# esp07_12_shift_inout.net
KiCad netlist of a schematic drawn in EAGLE
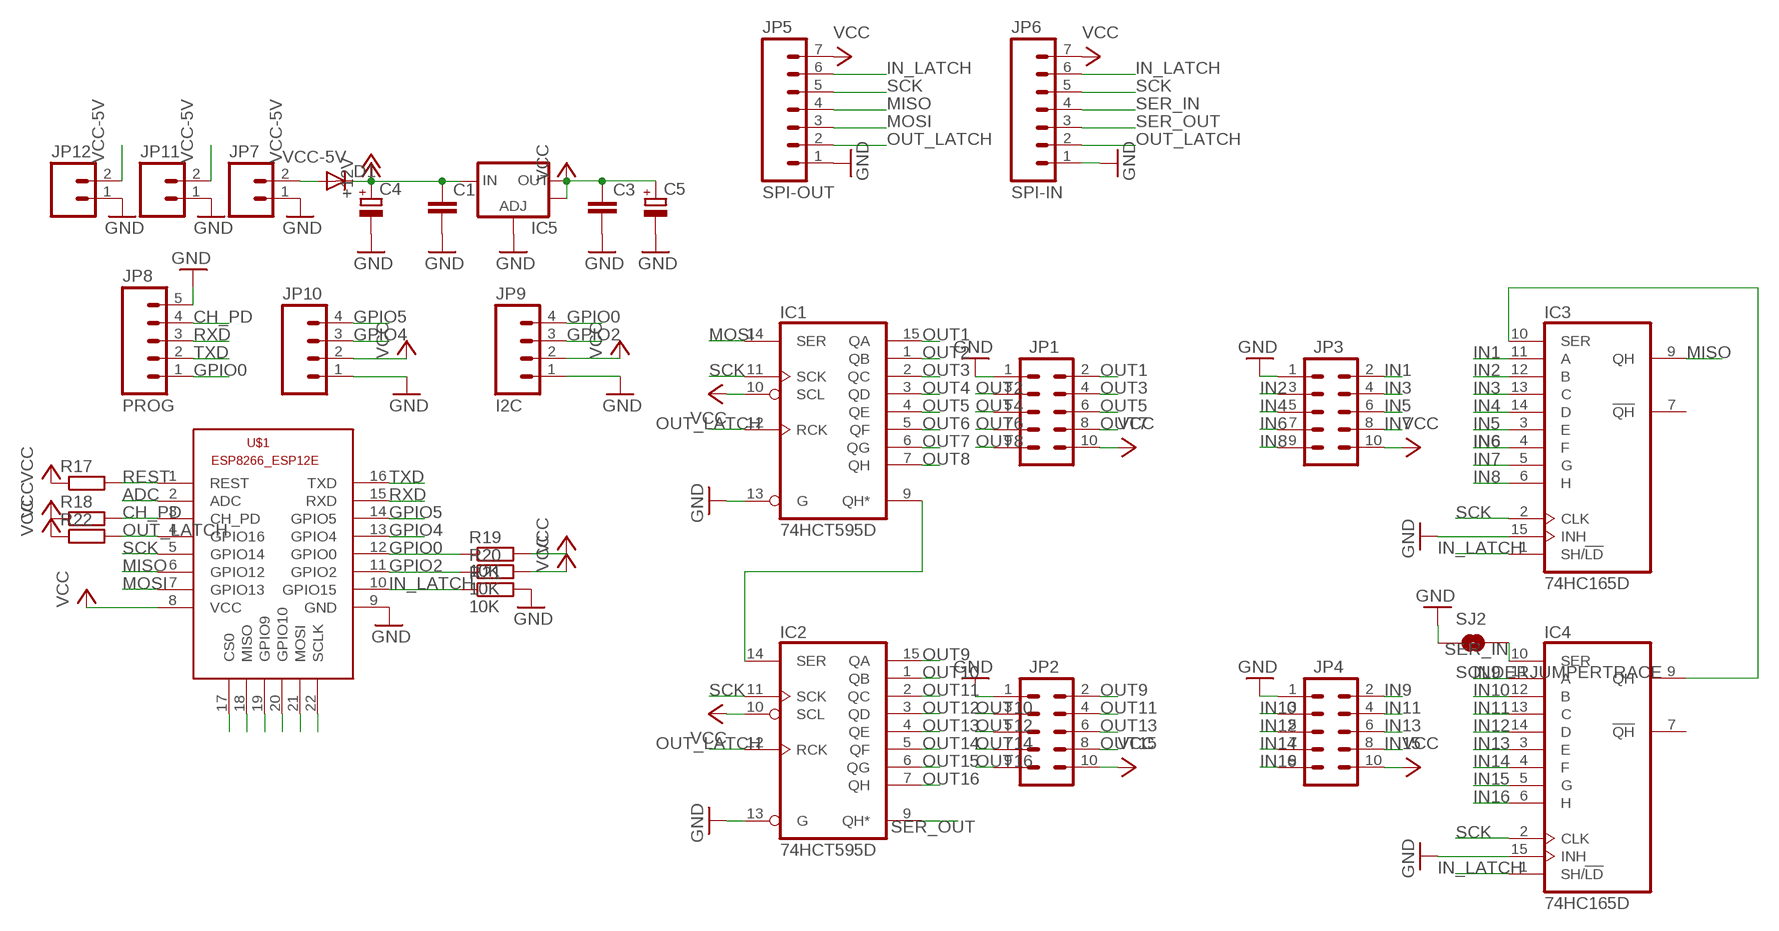
[diagram p0: schematic, sheet 1]

(export (version "E")
  (design (tool "Eeschema 10.0.6"))
  (components
    (comp (ref "C1")
      (value "C-EUC0805")
      (footprint "eagle-import:C0805")
      (libsource (lib "eagle-import") (part "C-EUC0805"))
    )
    (comp (ref "C3")
      (value "C-EUC0805")
      (footprint "eagle-import:C0805")
      (libsource (lib "eagle-import") (part "C-EUC0805"))
    )
    (comp (ref "C4")
      (value "CPOL-EUD/7343-31R")
      (footprint "eagle-import:D_7343-31R")
      (libsource (lib "eagle-import") (part "CPOL-EUD/7343-31R"))
    )
    (comp (ref "C5")
      (value "CPOL-EUD/7343-31R")
      (footprint "eagle-import:D_7343-31R")
      (libsource (lib "eagle-import") (part "CPOL-EUD/7343-31R"))
    )
    (comp (ref "D1")
      (value "DIODE-DO214AC")
      (footprint "eagle-import:DO214AC")
      (libsource (lib "eagle-import") (part "DIODE-DO214AC"))
    )
    (comp (ref "IC1")
      (value "74HCT595D")
      (footprint "eagle-import:SO16")
      (libsource (lib "eagle-import") (part "74595DHCT"))
    )
    (comp (ref "IC2")
      (value "74HCT595D")
      (footprint "eagle-import:SO16")
      (libsource (lib "eagle-import") (part "74595DHCT"))
    )
    (comp (ref "IC3")
      (value "74HC165D")
      (footprint "eagle-import:SO16")
      (libsource (lib "eagle-import") (part "74165DHC"))
    )
    (comp (ref "IC4")
      (value "74HC165D")
      (footprint "eagle-import:SO16")
      (libsource (lib "eagle-import") (part "74165DHC"))
    )
    (comp (ref "IC5")
      (value "V_REG_LM1117SOT223")
      (footprint "eagle-import:SOT223")
      (libsource (lib "eagle-import") (part "V_REG_LM1117SOT223"))
    )
    (comp (ref "JP1")
      (value "M05X2SHD")
      (footprint "eagle-import:2X5-SHROUDED")
      (libsource (lib "eagle-import") (part "M05X2SHD"))
    )
    (comp (ref "JP2")
      (value "M05X2SHD")
      (footprint "eagle-import:2X5-SHROUDED")
      (libsource (lib "eagle-import") (part "M05X2SHD"))
    )
    (comp (ref "JP3")
      (value "M05X2SHD")
      (footprint "eagle-import:2X5-SHROUDED")
      (libsource (lib "eagle-import") (part "M05X2SHD"))
    )
    (comp (ref "JP4")
      (value "M05X2SHD")
      (footprint "eagle-import:2X5-SHROUDED")
      (libsource (lib "eagle-import") (part "M05X2SHD"))
    )
    (comp (ref "JP5")
      (value "SPI-OUT")
      (footprint "eagle-import:1X07")
      (libsource (lib "eagle-import") (part "M07"))
    )
    (comp (ref "JP6")
      (value "SPI-IN")
      (footprint "eagle-import:1X07")
      (libsource (lib "eagle-import") (part "M07"))
    )
    (comp (ref "JP7")
      (value "M02PTH3")
      (footprint "eagle-import:1X02_LONGPADS")
      (libsource (lib "eagle-import") (part "M02PTH3"))
    )
    (comp (ref "JP8")
      (value "PROG")
      (footprint "eagle-import:1X05")
      (libsource (lib "eagle-import") (part "M05PTH"))
    )
    (comp (ref "JP9")
      (value "I2C")
      (footprint "eagle-import:1X04")
      (libsource (lib "eagle-import") (part "M04PTH"))
    )
    (comp (ref "JP10")
      (value "M04PTH")
      (footprint "eagle-import:1X04")
      (libsource (lib "eagle-import") (part "M04PTH"))
    )
    (comp (ref "JP11")
      (value "M02PTH")
      (footprint "eagle-import:1X02")
      (libsource (lib "eagle-import") (part "M02PTH"))
    )
    (comp (ref "JP12")
      (value "M02PTH")
      (footprint "eagle-import:1X02")
      (libsource (lib "eagle-import") (part "M02PTH"))
    )
    (comp (ref "R17")
      (value "R-EU_R0603")
      (footprint "eagle-import:R0603")
      (libsource (lib "eagle-import") (part "R-EU_R0603"))
    )
    (comp (ref "R18")
      (value "R-EU_R0603")
      (footprint "eagle-import:R0603")
      (libsource (lib "eagle-import") (part "R-EU_R0603"))
    )
    (comp (ref "R19")
      (value "10K")
      (footprint "eagle-import:R0603")
      (libsource (lib "eagle-import") (part "R-EU_R0603"))
    )
    (comp (ref "R20")
      (value "10K")
      (footprint "eagle-import:R0603")
      (libsource (lib "eagle-import") (part "R-EU_R0603"))
    )
    (comp (ref "R21")
      (value "10K")
      (footprint "eagle-import:R0603")
      (libsource (lib "eagle-import") (part "R-EU_R0603"))
    )
    (comp (ref "R22")
      (value "R-EU_R0603")
      (footprint "eagle-import:R0603")
      (libsource (lib "eagle-import") (part "R-EU_R0603"))
    )
    (comp (ref "SJ2")
      (value "SOLDERJUMPERTRACE")
      (footprint "eagle-import:SJ_2S-TRACE")
      (libsource (lib "eagle-import") (part "SOLDERJUMPERTRACE"))
    )
    (comp (ref "U$1")
      (value "ESP8266-12EESP8266-ESP12E")
      (footprint "eagle-import:ESP8266-ESP12E")
      (libsource (lib "eagle-import") (part "ESP8266-12EESP8266-ESP12E"))
    )
  )
  (nets
    (net (code "1") (name "+12V") (class "Default")
      (node (ref "C1") (pin "1") (pinfunction "1_1") (pintype "passive"))
      (node (ref "C4") (pin "+") (pinfunction "+_+") (pintype "passive"))
      (node (ref "D1") (pin "C") (pinfunction "C_C") (pintype "passive"))
      (node (ref "IC5") (pin "3") (pinfunction "IN_3") (pintype "input"))
    )
    (net (code "2") (name "/ADC") (class "Default")
      (node (ref "U$1") (pin "2") (pinfunction "ADC_2") (pintype "bidirectional"))
    )
    (net (code "3") (name "/CH_PD") (class "Default")
      (node (ref "JP8") (pin "4") (pinfunction "4_4") (pintype "passive"))
      (node (ref "R18") (pin "2") (pinfunction "2_2") (pintype "passive"))
      (node (ref "U$1") (pin "3") (pinfunction "CH_PD_3") (pintype "bidirectional"))
    )
    (net (code "4") (name "/GPIO0") (class "Default")
      (node (ref "JP8") (pin "1") (pinfunction "1_1") (pintype "passive"))
      (node (ref "JP9") (pin "4") (pinfunction "4_4") (pintype "passive"))
      (node (ref "R19") (pin "1") (pinfunction "1_1") (pintype "passive"))
      (node (ref "U$1") (pin "12") (pinfunction "GPIO0_12") (pintype "bidirectional"))
    )
    (net (code "5") (name "/GPIO2") (class "Default")
      (node (ref "JP9") (pin "3") (pinfunction "3_3") (pintype "passive"))
      (node (ref "R20") (pin "1") (pinfunction "1_1") (pintype "passive"))
      (node (ref "U$1") (pin "11") (pinfunction "GPIO2_11") (pintype "bidirectional"))
    )
    (net (code "6") (name "/GPIO4") (class "Default")
      (node (ref "JP10") (pin "3") (pinfunction "3_3") (pintype "passive"))
      (node (ref "U$1") (pin "13") (pinfunction "GPIO4_13") (pintype "bidirectional"))
    )
    (net (code "7") (name "/GPIO5") (class "Default")
      (node (ref "JP10") (pin "4") (pinfunction "4_4") (pintype "passive"))
      (node (ref "U$1") (pin "14") (pinfunction "GPIO5_14") (pintype "bidirectional"))
    )
    (net (code "8") (name "/IN1") (class "Default")
      (node (ref "IC3") (pin "11") (pinfunction "A_11") (pintype "input"))
      (node (ref "JP3") (pin "2") (pinfunction "2_2") (pintype "passive"))
    )
    (net (code "9") (name "/IN2") (class "Default")
      (node (ref "IC3") (pin "12") (pinfunction "B_12") (pintype "input"))
      (node (ref "JP3") (pin "3") (pinfunction "3_3") (pintype "passive"))
    )
    (net (code "10") (name "/IN3") (class "Default")
      (node (ref "IC3") (pin "13") (pinfunction "C_13") (pintype "input"))
      (node (ref "JP3") (pin "4") (pinfunction "4_4") (pintype "passive"))
    )
    (net (code "11") (name "/IN4") (class "Default")
      (node (ref "IC3") (pin "14") (pinfunction "D_14") (pintype "input"))
      (node (ref "JP3") (pin "5") (pinfunction "5_5") (pintype "passive"))
    )
    (net (code "12") (name "/IN5") (class "Default")
      (node (ref "IC3") (pin "3") (pinfunction "E_3") (pintype "input"))
      (node (ref "JP3") (pin "6") (pinfunction "6_6") (pintype "passive"))
    )
    (net (code "13") (name "/IN6") (class "Default")
      (node (ref "IC3") (pin "4") (pinfunction "F_4") (pintype "input"))
      (node (ref "JP3") (pin "7") (pinfunction "7_7") (pintype "passive"))
    )
    (net (code "14") (name "/IN7") (class "Default")
      (node (ref "IC3") (pin "5") (pinfunction "G_5") (pintype "input"))
      (node (ref "JP3") (pin "8") (pinfunction "8_8") (pintype "passive"))
    )
    (net (code "15") (name "/IN8") (class "Default")
      (node (ref "IC3") (pin "6") (pinfunction "H_6") (pintype "input"))
      (node (ref "JP3") (pin "9") (pinfunction "9_9") (pintype "passive"))
    )
    (net (code "16") (name "/IN9") (class "Default")
      (node (ref "IC4") (pin "11") (pinfunction "A_11") (pintype "input"))
      (node (ref "JP4") (pin "2") (pinfunction "2_2") (pintype "passive"))
    )
    (net (code "17") (name "/IN10") (class "Default")
      (node (ref "IC4") (pin "12") (pinfunction "B_12") (pintype "input"))
      (node (ref "JP4") (pin "3") (pinfunction "3_3") (pintype "passive"))
    )
    (net (code "18") (name "/IN11") (class "Default")
      (node (ref "IC4") (pin "13") (pinfunction "C_13") (pintype "input"))
      (node (ref "JP4") (pin "4") (pinfunction "4_4") (pintype "passive"))
    )
    (net (code "19") (name "/IN12") (class "Default")
      (node (ref "IC4") (pin "14") (pinfunction "D_14") (pintype "input"))
      (node (ref "JP4") (pin "5") (pinfunction "5_5") (pintype "passive"))
    )
    (net (code "20") (name "/IN13") (class "Default")
      (node (ref "IC4") (pin "3") (pinfunction "E_3") (pintype "input"))
      (node (ref "JP4") (pin "6") (pinfunction "6_6") (pintype "passive"))
    )
    (net (code "21") (name "/IN14") (class "Default")
      (node (ref "IC4") (pin "4") (pinfunction "F_4") (pintype "input"))
      (node (ref "JP4") (pin "7") (pinfunction "7_7") (pintype "passive"))
    )
    (net (code "22") (name "/IN15") (class "Default")
      (node (ref "IC4") (pin "5") (pinfunction "G_5") (pintype "input"))
      (node (ref "JP4") (pin "8") (pinfunction "8_8") (pintype "passive"))
    )
    (net (code "23") (name "/IN16") (class "Default")
      (node (ref "IC4") (pin "6") (pinfunction "H_6") (pintype "input"))
      (node (ref "JP4") (pin "9") (pinfunction "9_9") (pintype "passive"))
    )
    (net (code "24") (name "/IN_LATCH") (class "Default")
      (node (ref "IC3") (pin "1") (pinfunction "SH/~{LD}_1") (pintype "input"))
      (node (ref "IC4") (pin "1") (pinfunction "SH/~{LD}_1") (pintype "input"))
      (node (ref "JP5") (pin "6") (pinfunction "6_6") (pintype "passive"))
      (node (ref "JP6") (pin "6") (pinfunction "6_6") (pintype "passive"))
      (node (ref "R21") (pin "1") (pinfunction "1_1") (pintype "passive"))
      (node (ref "U$1") (pin "10") (pinfunction "GPIO15_10") (pintype "bidirectional"))
    )
    (net (code "25") (name "/MISO") (class "Default")
      (node (ref "IC3") (pin "9") (pinfunction "QH_9") (pintype "output"))
      (node (ref "JP5") (pin "4") (pinfunction "4_4") (pintype "passive"))
      (node (ref "U$1") (pin "6") (pinfunction "GPIO12_6") (pintype "bidirectional"))
    )
    (net (code "26") (name "/MOSI") (class "Default")
      (node (ref "IC1") (pin "14") (pinfunction "SER_14") (pintype "input"))
      (node (ref "JP5") (pin "3") (pinfunction "3_3") (pintype "passive"))
      (node (ref "U$1") (pin "7") (pinfunction "GPIO13_7") (pintype "bidirectional"))
    )
    (net (code "27") (name "/OUT1") (class "Default")
      (node (ref "IC1") (pin "15") (pinfunction "QA_15") (pintype "tri_state"))
      (node (ref "JP1") (pin "2") (pinfunction "2_2") (pintype "passive"))
    )
    (net (code "28") (name "/OUT2") (class "Default")
      (node (ref "IC1") (pin "1") (pinfunction "QB_1") (pintype "tri_state"))
      (node (ref "JP1") (pin "3") (pinfunction "3_3") (pintype "passive"))
    )
    (net (code "29") (name "/OUT3") (class "Default")
      (node (ref "IC1") (pin "2") (pinfunction "QC_2") (pintype "tri_state"))
      (node (ref "JP1") (pin "4") (pinfunction "4_4") (pintype "passive"))
    )
    (net (code "30") (name "/OUT4") (class "Default")
      (node (ref "IC1") (pin "3") (pinfunction "QD_3") (pintype "tri_state"))
      (node (ref "JP1") (pin "5") (pinfunction "5_5") (pintype "passive"))
    )
    (net (code "31") (name "/OUT5") (class "Default")
      (node (ref "IC1") (pin "4") (pinfunction "QE_4") (pintype "tri_state"))
      (node (ref "JP1") (pin "6") (pinfunction "6_6") (pintype "passive"))
    )
    (net (code "32") (name "/OUT6") (class "Default")
      (node (ref "IC1") (pin "5") (pinfunction "QF_5") (pintype "tri_state"))
      (node (ref "JP1") (pin "7") (pinfunction "7_7") (pintype "passive"))
    )
    (net (code "33") (name "/OUT7") (class "Default")
      (node (ref "IC1") (pin "6") (pinfunction "QG_6") (pintype "tri_state"))
      (node (ref "JP1") (pin "8") (pinfunction "8_8") (pintype "passive"))
    )
    (net (code "34") (name "/OUT8") (class "Default")
      (node (ref "IC1") (pin "7") (pinfunction "QH_7") (pintype "tri_state"))
      (node (ref "JP1") (pin "9") (pinfunction "9_9") (pintype "passive"))
    )
    (net (code "35") (name "/OUT9") (class "Default")
      (node (ref "IC2") (pin "15") (pinfunction "QA_15") (pintype "tri_state"))
      (node (ref "JP2") (pin "2") (pinfunction "2_2") (pintype "passive"))
    )
    (net (code "36") (name "/OUT10") (class "Default")
      (node (ref "IC2") (pin "1") (pinfunction "QB_1") (pintype "tri_state"))
      (node (ref "JP2") (pin "3") (pinfunction "3_3") (pintype "passive"))
    )
    (net (code "37") (name "/OUT11") (class "Default")
      (node (ref "IC2") (pin "2") (pinfunction "QC_2") (pintype "tri_state"))
      (node (ref "JP2") (pin "4") (pinfunction "4_4") (pintype "passive"))
    )
    (net (code "38") (name "/OUT12") (class "Default")
      (node (ref "IC2") (pin "3") (pinfunction "QD_3") (pintype "tri_state"))
      (node (ref "JP2") (pin "5") (pinfunction "5_5") (pintype "passive"))
    )
    (net (code "39") (name "/OUT13") (class "Default")
      (node (ref "IC2") (pin "4") (pinfunction "QE_4") (pintype "tri_state"))
      (node (ref "JP2") (pin "6") (pinfunction "6_6") (pintype "passive"))
    )
    (net (code "40") (name "/OUT14") (class "Default")
      (node (ref "IC2") (pin "5") (pinfunction "QF_5") (pintype "tri_state"))
      (node (ref "JP2") (pin "7") (pinfunction "7_7") (pintype "passive"))
    )
    (net (code "41") (name "/OUT15") (class "Default")
      (node (ref "IC2") (pin "6") (pinfunction "QG_6") (pintype "tri_state"))
      (node (ref "JP2") (pin "8") (pinfunction "8_8") (pintype "passive"))
    )
    (net (code "42") (name "/OUT16") (class "Default")
      (node (ref "IC2") (pin "7") (pinfunction "QH_7") (pintype "tri_state"))
      (node (ref "JP2") (pin "9") (pinfunction "9_9") (pintype "passive"))
    )
    (net (code "43") (name "/OUT_LATCH") (class "Default")
      (node (ref "IC1") (pin "12") (pinfunction "RCK_12") (pintype "input"))
      (node (ref "IC2") (pin "12") (pinfunction "RCK_12") (pintype "input"))
      (node (ref "JP5") (pin "2") (pinfunction "2_2") (pintype "passive"))
      (node (ref "JP6") (pin "2") (pinfunction "2_2") (pintype "passive"))
      (node (ref "R22") (pin "2") (pinfunction "2_2") (pintype "passive"))
      (node (ref "U$1") (pin "4") (pinfunction "GPIO16_4") (pintype "bidirectional"))
    )
    (net (code "44") (name "/REST") (class "Default")
      (node (ref "R17") (pin "2") (pinfunction "2_2") (pintype "passive"))
      (node (ref "U$1") (pin "1") (pinfunction "REST_1") (pintype "bidirectional"))
    )
    (net (code "45") (name "/RXD") (class "Default")
      (node (ref "JP8") (pin "3") (pinfunction "3_3") (pintype "passive"))
      (node (ref "U$1") (pin "15") (pinfunction "RXD_15") (pintype "bidirectional"))
    )
    (net (code "46") (name "/SCK") (class "Default")
      (node (ref "IC1") (pin "11") (pinfunction "SCK_11") (pintype "input"))
      (node (ref "IC2") (pin "11") (pinfunction "SCK_11") (pintype "input"))
      (node (ref "IC3") (pin "2") (pinfunction "CLK_2") (pintype "input"))
      (node (ref "IC4") (pin "2") (pinfunction "CLK_2") (pintype "input"))
      (node (ref "JP5") (pin "5") (pinfunction "5_5") (pintype "passive"))
      (node (ref "JP6") (pin "5") (pinfunction "5_5") (pintype "passive"))
      (node (ref "U$1") (pin "5") (pinfunction "GPIO14_5") (pintype "bidirectional"))
    )
    (net (code "47") (name "/SER_IN") (class "Default")
      (node (ref "IC4") (pin "10") (pinfunction "SER_10") (pintype "input"))
      (node (ref "JP6") (pin "4") (pinfunction "4_4") (pintype "passive"))
      (node (ref "SJ2") (pin "2") (pinfunction "2_2") (pintype "passive"))
    )
    (net (code "48") (name "/SER_OUT") (class "Default")
      (node (ref "IC2") (pin "9") (pinfunction "QH*_9") (pintype "tri_state"))
      (node (ref "JP6") (pin "3") (pinfunction "3_3") (pintype "passive"))
    )
    (net (code "49") (name "/TXD") (class "Default")
      (node (ref "JP8") (pin "2") (pinfunction "2_2") (pintype "passive"))
      (node (ref "U$1") (pin "16") (pinfunction "TXD_16") (pintype "bidirectional"))
    )
    (net (code "50") (name "/VCC-5V") (class "Default")
      (node (ref "D1") (pin "A") (pinfunction "A_A") (pintype "passive"))
      (node (ref "JP11") (pin "2") (pinfunction "2_2") (pintype "passive"))
      (node (ref "JP12") (pin "2") (pinfunction "2_2") (pintype "passive"))
      (node (ref "JP7") (pin "2") (pinfunction "2_2") (pintype "passive"))
    )
    (net (code "51") (name "GND") (class "Default")
      (node (ref "C1") (pin "2") (pinfunction "2_2") (pintype "passive"))
      (node (ref "C3") (pin "2") (pinfunction "2_2") (pintype "passive"))
      (node (ref "C4") (pin "-") (pinfunction "-_-") (pintype "passive"))
      (node (ref "C5") (pin "-") (pinfunction "-_-") (pintype "passive"))
      (node (ref "IC1") (pin "13") (pinfunction "G_13") (pintype "input"))
      (node (ref "IC2") (pin "13") (pinfunction "G_13") (pintype "input"))
      (node (ref "IC3") (pin "15") (pinfunction "INH_15") (pintype "input"))
      (node (ref "IC4") (pin "15") (pinfunction "INH_15") (pintype "input"))
      (node (ref "IC5") (pin "1") (pinfunction "ADJ_1") (pintype "input"))
      (node (ref "JP1") (pin "1") (pinfunction "1_1") (pintype "passive"))
      (node (ref "JP10") (pin "1") (pinfunction "1_1") (pintype "passive"))
      (node (ref "JP11") (pin "1") (pinfunction "1_1") (pintype "passive"))
      (node (ref "JP12") (pin "1") (pinfunction "1_1") (pintype "passive"))
      (node (ref "JP2") (pin "1") (pinfunction "1_1") (pintype "passive"))
      (node (ref "JP3") (pin "1") (pinfunction "1_1") (pintype "passive"))
      (node (ref "JP4") (pin "1") (pinfunction "1_1") (pintype "passive"))
      (node (ref "JP5") (pin "1") (pinfunction "1_1") (pintype "passive"))
      (node (ref "JP6") (pin "1") (pinfunction "1_1") (pintype "passive"))
      (node (ref "JP7") (pin "1") (pinfunction "1_1") (pintype "passive"))
      (node (ref "JP8") (pin "5") (pinfunction "5_5") (pintype "passive"))
      (node (ref "JP9") (pin "1") (pinfunction "1_1") (pintype "passive"))
      (node (ref "R21") (pin "2") (pinfunction "2_2") (pintype "passive"))
      (node (ref "SJ2") (pin "1") (pinfunction "1_1") (pintype "passive"))
      (node (ref "U$1") (pin "9") (pinfunction "GND_9") (pintype "bidirectional"))
    )
    (net (code "52") (name "Net-(IC1A-QH*)") (class "Default")
      (node (ref "IC1") (pin "9") (pinfunction "QH*_9") (pintype "tri_state"))
      (node (ref "IC2") (pin "14") (pinfunction "SER_14") (pintype "input"))
    )
    (net (code "53") (name "Net-(IC3A-SER)") (class "Default")
      (node (ref "IC3") (pin "10") (pinfunction "SER_10") (pintype "input"))
      (node (ref "IC4") (pin "9") (pinfunction "QH_9") (pintype "output"))
    )
    (net (code "54") (name "VCC") (class "Default")
      (node (ref "C3") (pin "1") (pinfunction "1_1") (pintype "passive"))
      (node (ref "C5") (pin "+") (pinfunction "+_+") (pintype "passive"))
      (node (ref "IC1") (pin "10") (pinfunction "SCL_10") (pintype "input"))
      (node (ref "IC2") (pin "10") (pinfunction "SCL_10") (pintype "input"))
      (node (ref "IC5") (pin "2") (pinfunction "OUT_2") (pintype "output"))
      (node (ref "IC5") (pin "4") (pinfunction "OUT_4") (pintype "output"))
      (node (ref "JP1") (pin "10") (pinfunction "10_10") (pintype "passive"))
      (node (ref "JP10") (pin "2") (pinfunction "2_2") (pintype "passive"))
      (node (ref "JP2") (pin "10") (pinfunction "10_10") (pintype "passive"))
      (node (ref "JP3") (pin "10") (pinfunction "10_10") (pintype "passive"))
      (node (ref "JP4") (pin "10") (pinfunction "10_10") (pintype "passive"))
      (node (ref "JP5") (pin "7") (pinfunction "7_7") (pintype "passive"))
      (node (ref "JP6") (pin "7") (pinfunction "7_7") (pintype "passive"))
      (node (ref "JP9") (pin "2") (pinfunction "2_2") (pintype "passive"))
      (node (ref "R17") (pin "1") (pinfunction "1_1") (pintype "passive"))
      (node (ref "R18") (pin "1") (pinfunction "1_1") (pintype "passive"))
      (node (ref "R19") (pin "2") (pinfunction "2_2") (pintype "passive"))
      (node (ref "R20") (pin "2") (pinfunction "2_2") (pintype "passive"))
      (node (ref "R22") (pin "1") (pinfunction "1_1") (pintype "passive"))
      (node (ref "U$1") (pin "8") (pinfunction "VCC_8") (pintype "bidirectional"))
    )
    (net (code "55") (name "unconnected-(IC3A-~{QH}-Pad7)") (class "Default")
      (node (ref "IC3") (pin "7") (pinfunction "~{QH}_7") (pintype "output"))
    )
    (net (code "56") (name "unconnected-(IC4A-~{QH}-Pad7)") (class "Default")
      (node (ref "IC4") (pin "7") (pinfunction "~{QH}_7") (pintype "output"))
    )
    (net (code "57") (name "unconnected-(U$1-CS0-Pad17)") (class "Default")
      (node (ref "U$1") (pin "17") (pinfunction "CS0_17") (pintype "bidirectional"))
    )
    (net (code "58") (name "unconnected-(U$1-GPIO9-Pad19)") (class "Default")
      (node (ref "U$1") (pin "19") (pinfunction "GPIO9_19") (pintype "bidirectional"))
    )
    (net (code "59") (name "unconnected-(U$1-GPIO10-Pad20)") (class "Default")
      (node (ref "U$1") (pin "20") (pinfunction "GPIO10_20") (pintype "bidirectional"))
    )
    (net (code "60") (name "unconnected-(U$1-MISO-Pad18)") (class "Default")
      (node (ref "U$1") (pin "18") (pinfunction "MISO_18") (pintype "bidirectional"))
    )
    (net (code "61") (name "unconnected-(U$1-MOSI-Pad21)") (class "Default")
      (node (ref "U$1") (pin "21") (pinfunction "MOSI_21") (pintype "bidirectional"))
    )
    (net (code "62") (name "unconnected-(U$1-SCLK-Pad22)") (class "Default")
      (node (ref "U$1") (pin "22") (pinfunction "SCLK_22") (pintype "bidirectional"))
    )
  )
)
